# logger_periph.net
KiCad netlist of a schematic drawn in Altium Designer
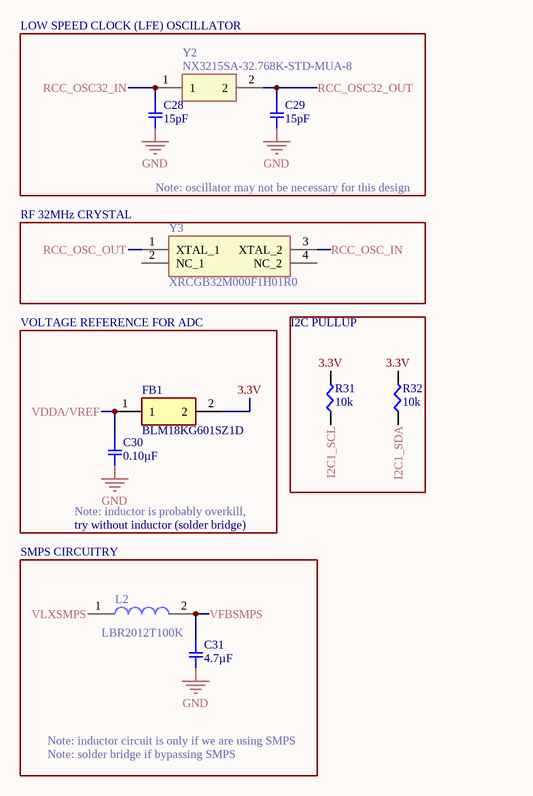
[diagram p0: logger_periph.SchDoc]

(export (version "E")
  (design (tool "Eeschema 10.0.6"))
  (components
    (comp (ref "C28")
      (value "15pF")
      (footprint "SMD-0402C")
      (description "CAP CER 15PF 50V NP0 0402")
      (fields
        (field (name "DIGI-KEY PART NUMBER") "490-11147-1-ND")
        (field (name "PART NUMBER") "GCM1555C1H150JA16D")
      )
      (libsource (lib "capacitor_murata_0402") (part "GCM1555C1H150JA16D"))
    )
    (comp (ref "C29")
      (value "15pF")
      (footprint "SMD-0402C")
      (description "CAP CER 15PF 50V NP0 0402")
      (fields
        (field (name "DIGI-KEY PART NUMBER") "490-11147-1-ND")
        (field (name "PART NUMBER") "GCM1555C1H150JA16D")
      )
      (libsource (lib "capacitor_murata_0402") (part "GCM1555C1H150JA16D"))
    )
    (comp (ref "C30")
      (value "0.10µF")
      (footprint "SMD-0402C")
      (description "CAP CER 0.1UF 16V X7R 0402")
      (fields
        (field (name "DIGI-KEY PART NUMBER") "490-4759-1-ND")
        (field (name "PART NUMBER") "GCM155R71C104KA55D")
      )
      (libsource (lib "capacitor_murata_0402") (part "GCM155R71C104KA55D"))
    )
    (comp (ref "C31")
      (value "4.7µF")
      (footprint "SMD-0402C")
      (description "CAP CER 4.7UF 4V X5R 0402")
      (fields
        (field (name "DIGI-KEY PART NUMBER") "490-13231-1-ND")
        (field (name "PART NUMBER") "GRM153R60G475ME15D")
      )
      (libsource (lib "capacitor_murata_0402") (part "GRM153R60G475ME15D"))
    )
    (comp (ref "FB1")
      (value "BLM18KG601SZ1D")
      (footprint "SamacSys:BEADC1608X95N")
      (description "Ferrite Bead")
      (fields (field (name "MOUSER PART NUMBER") "81-BLM18KG601SZ1D"))
      (libsource (lib "*") (part "BLM18KG601SZ1D"))
    )
    (comp (ref "L2")
      (value "LBR2012T100K")
      (footprint "SamacSys:INDC2012X145N")
      (description "Inductor")
      (fields (field (name "MOUSER PART NUMBER") "963-LBR2012T100K"))
      (libsource (lib "SamacSys") (part "LBR2012T100K"))
    )
    (comp (ref "R31")
      (value "10k")
      (footprint "SMD-0402-RES")
      (description "RES SMD 10K OHM 5% 1/10W 0402")
      (fields (field (name "PART NUMBER") "ERJ-2GEJ103X") (field (name "DIGI-KEY PART NUMBER") "P10KJCT-ND"))
      (libsource (lib "Panasonic_ERJ_0402") (part "ERJ-2GEJ103X"))
    )
    (comp (ref "R32")
      (value "10k")
      (footprint "SMD-0402-RES")
      (description "RES SMD 10K OHM 5% 1/10W 0402")
      (fields (field (name "PART NUMBER") "ERJ-2GEJ103X") (field (name "DIGI-KEY PART NUMBER") "P10KJCT-ND"))
      (libsource (lib "Panasonic_ERJ_0402") (part "ERJ-2GEJ103X"))
    )
    (comp (ref "Y2")
      (value "NX3215SA-32.768K-STD-MUA-8")
      (footprint "NX3215SA")
      (description "Crystal or Oscillator")
      (fields (field (name "MOUSER PART NUMBER") "344-NX3215SA32768K8"))
      (libsource (lib "SamacSys") (part "NX3215SA-32.768K-STD-MUA-8"))
    )
    (comp (ref "Y3")
      (value "XRCGB32M000F1H01R0")
      (footprint "XRCGB32M000F1H01R0")
      (description "Crystal or Oscillator")
      (fields (field (name "MOUSER PART NUMBER") "81-XRCGB32M000F1H01R"))
      (libsource (lib "SamacSys") (part "XRCGB32M000F1H01R0"))
    )
  )
  (nets
    (net (code "1") (name "/3.3V") (class "Default")
      (node (ref "FB1") (pin "2") (pinfunction "2_2") (pintype "passive"))
      (node (ref "R31") (pin "2") (pinfunction "2_2") (pintype "passive"))
      (node (ref "R32") (pin "2") (pinfunction "2_2") (pintype "passive"))
    )
    (net (code "2") (name "/I2C1_SCL") (class "Default")
      (node (ref "R31") (pin "1") (pinfunction "1_1") (pintype "passive"))
    )
    (net (code "3") (name "/I2C1_SDA") (class "Default")
      (node (ref "R32") (pin "1") (pinfunction "1_1") (pintype "passive"))
    )
    (net (code "4") (name "/RCC_OSC32_IN") (class "Default")
      (node (ref "C28") (pin "1") (pinfunction "1_1") (pintype "passive"))
      (node (ref "Y2") (pin "1") (pinfunction "1_1") (pintype "passive"))
    )
    (net (code "5") (name "/RCC_OSC32_OUT") (class "Default")
      (node (ref "C29") (pin "1") (pinfunction "1_1") (pintype "passive"))
      (node (ref "Y2") (pin "2") (pinfunction "2_2") (pintype "passive"))
    )
    (net (code "6") (name "/RCC_OSC_IN") (class "Default")
      (node (ref "Y3") (pin "3") (pinfunction "XTAL_2_3") (pintype "passive"))
    )
    (net (code "7") (name "/RCC_OSC_OUT") (class "Default")
      (node (ref "Y3") (pin "1") (pinfunction "XTAL_1_1") (pintype "passive"))
    )
    (net (code "8") (name "/VDDA{slash}VREF") (class "Default")
      (node (ref "C30") (pin "1") (pinfunction "1_1") (pintype "passive"))
      (node (ref "FB1") (pin "1") (pinfunction "1_1") (pintype "passive"))
    )
    (net (code "9") (name "/VFBSMPS") (class "Default")
      (node (ref "C31") (pin "1") (pinfunction "1_1") (pintype "passive"))
      (node (ref "L2") (pin "2") (pinfunction "2_2") (pintype "passive"))
    )
    (net (code "10") (name "/VLXSMPS") (class "Default")
      (node (ref "L2") (pin "1") (pinfunction "1_1") (pintype "passive"))
    )
    (net (code "11") (name "GND") (class "Default")
      (node (ref "C28") (pin "2") (pinfunction "2_2") (pintype "passive"))
      (node (ref "C29") (pin "2") (pinfunction "2_2") (pintype "passive"))
      (node (ref "C30") (pin "2") (pinfunction "2_2") (pintype "passive"))
      (node (ref "C31") (pin "2") (pinfunction "2_2") (pintype "passive"))
    )
    (net (code "12") (name "unconnected-(Y3-NC_1-Pad2)") (class "Default")
      (node (ref "Y3") (pin "2") (pinfunction "NC_1_2") (pintype "passive"))
    )
    (net (code "13") (name "unconnected-(Y3-NC_2-Pad4)") (class "Default")
      (node (ref "Y3") (pin "4") (pinfunction "NC_2_4") (pintype "passive"))
    )
  )
)
